# Rover_MDrv_V1_Sch.net
KiCad netlist of a schematic drawn in EAGLE
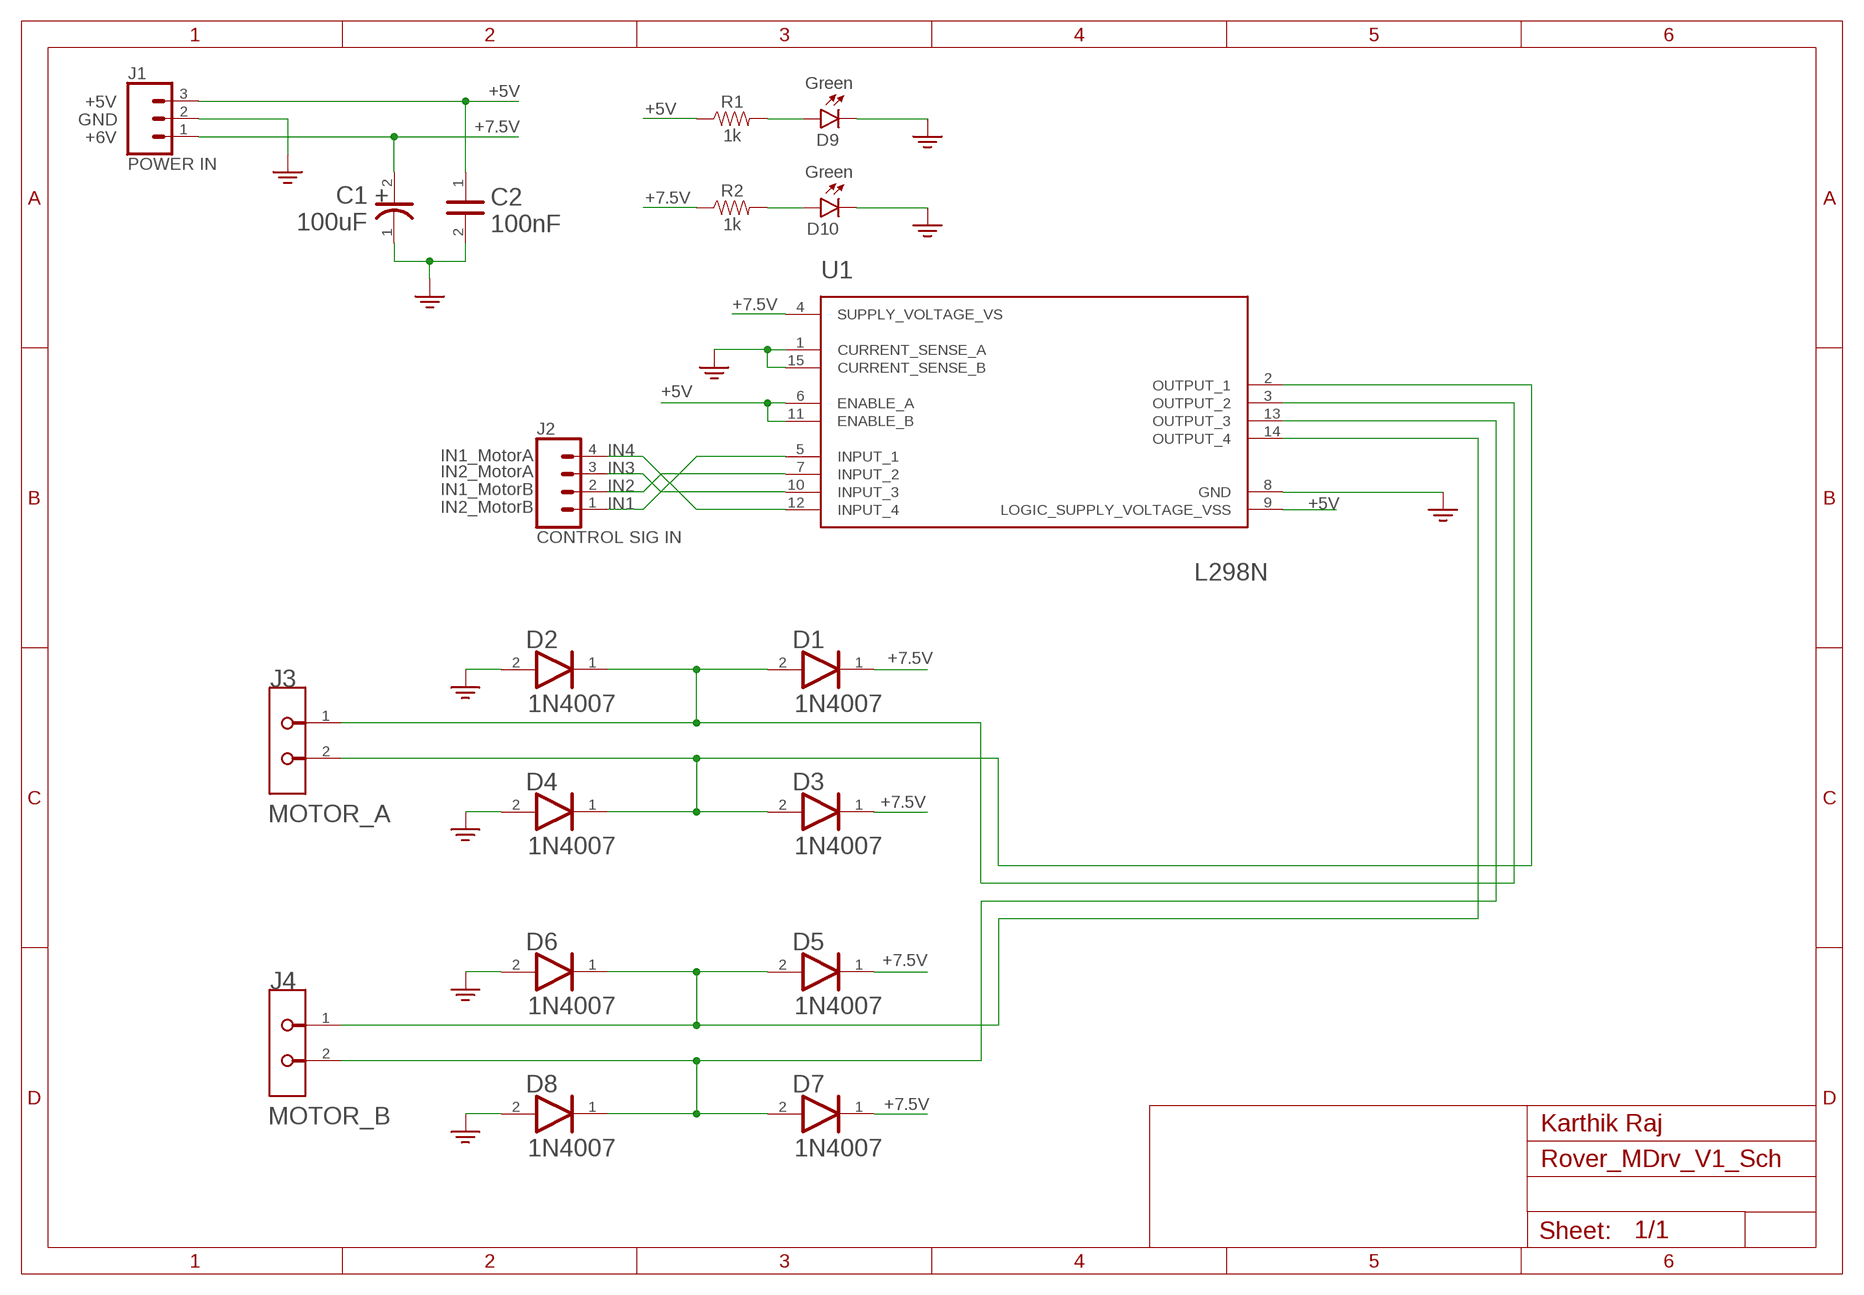
[diagram p0: schematic, sheet 1]

(export (version "E")
  (design (tool "Eeschema 10.0.6"))
  (components
    (comp (ref "C1")
      (value "100uF")
      (footprint "eagle-import:PANASONIC_EEU-FR1C101_0")
      (fields
        (field (name "DIGIKEY_PART_NUMBER") "P14391-ND")
        (field (name "MF") "Panasonic")
        (field (name "MOUSER_PART_NUMBER") "667-EEU-FR1C101")
      )
      (libsource (lib "eagle-import") (part "PANASONIC_EEU-FR1C101PANASONIC_EEU-FR1C101_0_0"))
    )
    (comp (ref "C2")
      (value "100nF")
      (footprint "eagle-import:AVX_CK05BX104K_0")
      (fields
        (field (name "DIGIKEY_PART_NUMBER") "1010-1198-ND")
        (field (name "MF") "AVX")
        (field (name "MOUSER_PART_NUMBER") "581-CK05BX104K")
      )
      (libsource (lib "eagle-import") (part "AVX_CK05BX104KAVX_CK05BX104K_0_0"))
    )
    (comp (ref "D1")
      (value "DIOTEC_1N4007DIOTEC_1N4007_0_0")
      (footprint "eagle-import:DIOTEC_1N4007_0")
      (fields (field (name "MF") "Diotec") (field (name "MPN") "1N4007"))
      (libsource (lib "eagle-import") (part "DIOTEC_1N4007DIOTEC_1N4007_0_0"))
    )
    (comp (ref "D2")
      (value "DIOTEC_1N4007DIOTEC_1N4007_0_0")
      (footprint "eagle-import:DIOTEC_1N4007_0")
      (fields (field (name "MF") "Diotec") (field (name "MPN") "1N4007"))
      (libsource (lib "eagle-import") (part "DIOTEC_1N4007DIOTEC_1N4007_0_0"))
    )
    (comp (ref "D3")
      (value "DIOTEC_1N4007DIOTEC_1N4007_0_0")
      (footprint "eagle-import:DIOTEC_1N4007_0")
      (fields (field (name "MF") "Diotec") (field (name "MPN") "1N4007"))
      (libsource (lib "eagle-import") (part "DIOTEC_1N4007DIOTEC_1N4007_0_0"))
    )
    (comp (ref "D4")
      (value "DIOTEC_1N4007DIOTEC_1N4007_0_0")
      (footprint "eagle-import:DIOTEC_1N4007_0")
      (fields (field (name "MF") "Diotec") (field (name "MPN") "1N4007"))
      (libsource (lib "eagle-import") (part "DIOTEC_1N4007DIOTEC_1N4007_0_0"))
    )
    (comp (ref "D5")
      (value "DIOTEC_1N4007DIOTEC_1N4007_0_0")
      (footprint "eagle-import:DIOTEC_1N4007_0")
      (fields (field (name "MF") "Diotec") (field (name "MPN") "1N4007"))
      (libsource (lib "eagle-import") (part "DIOTEC_1N4007DIOTEC_1N4007_0_0"))
    )
    (comp (ref "D6")
      (value "DIOTEC_1N4007DIOTEC_1N4007_0_0")
      (footprint "eagle-import:DIOTEC_1N4007_0")
      (fields (field (name "MF") "Diotec") (field (name "MPN") "1N4007"))
      (libsource (lib "eagle-import") (part "DIOTEC_1N4007DIOTEC_1N4007_0_0"))
    )
    (comp (ref "D7")
      (value "DIOTEC_1N4007DIOTEC_1N4007_0_0")
      (footprint "eagle-import:DIOTEC_1N4007_0")
      (fields (field (name "MF") "Diotec") (field (name "MPN") "1N4007"))
      (libsource (lib "eagle-import") (part "DIOTEC_1N4007DIOTEC_1N4007_0_0"))
    )
    (comp (ref "D8")
      (value "DIOTEC_1N4007DIOTEC_1N4007_0_0")
      (footprint "eagle-import:DIOTEC_1N4007_0")
      (fields (field (name "MF") "Diotec") (field (name "MPN") "1N4007"))
      (libsource (lib "eagle-import") (part "DIOTEC_1N4007DIOTEC_1N4007_0_0"))
    )
    (comp (ref "D9")
      (value "Green")
      (footprint "eagle-import:LED_3MM")
      (libsource (lib "eagle-import") (part "LED3MM"))
    )
    (comp (ref "D10")
      (value "Green")
      (footprint "eagle-import:LED_3MM")
      (libsource (lib "eagle-import") (part "LED3MM"))
    )
    (comp (ref "J1")
      (value "POWER IN")
      (footprint "eagle-import:1X03")
      (libsource (lib "eagle-import") (part "CONN_03"))
    )
    (comp (ref "J2")
      (value "CONTROL SIG IN")
      (footprint "eagle-import:1X04")
      (libsource (lib "eagle-import") (part "CONN_04PTH"))
    )
    (comp (ref "J3")
      (value "MOTOR_A")
      (footprint "eagle-import:TE_282837-2_0")
      (fields
        (field (name "DIGIKEY_PART_NUMBER") "A113320-ND")
        (field (name "MF") "TE")
        (field (name "MOUSER_PART_NUMBER") "571-2828372")
      )
      (libsource (lib "eagle-import") (part "TE_282837-2TE_282837-2_0_0"))
    )
    (comp (ref "J4")
      (value "MOTOR_B")
      (footprint "eagle-import:TE_282837-2_0")
      (fields
        (field (name "DIGIKEY_PART_NUMBER") "A113320-ND")
        (field (name "MF") "TE")
        (field (name "MOUSER_PART_NUMBER") "571-2828372")
      )
      (libsource (lib "eagle-import") (part "TE_282837-2TE_282837-2_0_0"))
    )
    (comp (ref "R1")
      (value "1k")
      (footprint "eagle-import:AXIAL-0.3")
      (libsource (lib "eagle-import") (part "RESISTORAXIAL-0.3"))
    )
    (comp (ref "R2")
      (value "1k")
      (footprint "eagle-import:AXIAL-0.3")
      (libsource (lib "eagle-import") (part "RESISTORAXIAL-0.3"))
    )
    (comp (ref "U1")
      (value "STMICROELECTRONICS_L298NSTMICROELECTRONICS_L298N_0_0")
      (footprint "eagle-import:STMICROELECTRONICS_L298N_0")
      (fields
        (field (name "DIGIKEY_PART_NUMBER") "497-1395-5-ND")
        (field (name "MF") "STMicroelectronics")
        (field (name "MOUSER_PART_NUMBER") "511-L298")
      )
      (libsource (lib "eagle-import") (part "STMICROELECTRONICS_L298NSTMICROELECTRONICS_L298N_0_0"))
    )
  )
  (nets
    (net (code "1") (name "/+5V") (class "Default")
      (node (ref "C2") (pin "1") (pinfunction "1_1") (pintype "bidirectional"))
      (node (ref "J1") (pin "3") (pinfunction "3_3") (pintype "passive"))
      (node (ref "R1") (pin "P$1") (pinfunction "1_P$1") (pintype "passive"))
      (node (ref "U1") (pin "11") (pinfunction "ENABLE_B_11") (pintype "bidirectional"))
      (node (ref "U1") (pin "6") (pinfunction "ENABLE_A_6") (pintype "bidirectional"))
      (node (ref "U1") (pin "9") (pinfunction "LOGIC_SUPPLY_VOLTAGE_VSS_9") (pintype "bidirectional"))
    )
    (net (code "2") (name "/+7.5V") (class "Default")
      (node (ref "C1") (pin "2") (pinfunction "ANODE_2") (pintype "bidirectional"))
      (node (ref "D1") (pin "1") (pinfunction "CATHODE_1") (pintype "passive"))
      (node (ref "D3") (pin "1") (pinfunction "CATHODE_1") (pintype "passive"))
      (node (ref "D5") (pin "1") (pinfunction "CATHODE_1") (pintype "passive"))
      (node (ref "D7") (pin "1") (pinfunction "CATHODE_1") (pintype "passive"))
      (node (ref "J1") (pin "1") (pinfunction "1_1") (pintype "passive"))
      (node (ref "R2") (pin "P$1") (pinfunction "1_P$1") (pintype "passive"))
      (node (ref "U1") (pin "4") (pinfunction "SUPPLY_VOLTAGE_VS_4") (pintype "bidirectional"))
    )
    (net (code "3") (name "/IN1") (class "Default")
      (node (ref "J2") (pin "1") (pinfunction "1_1") (pintype "passive"))
      (node (ref "U1") (pin "5") (pinfunction "INPUT_1_5") (pintype "bidirectional"))
    )
    (net (code "4") (name "/IN2") (class "Default")
      (node (ref "J2") (pin "2") (pinfunction "2_2") (pintype "passive"))
      (node (ref "U1") (pin "7") (pinfunction "INPUT_2_7") (pintype "bidirectional"))
    )
    (net (code "5") (name "/IN3") (class "Default")
      (node (ref "J2") (pin "3") (pinfunction "3_3") (pintype "passive"))
      (node (ref "U1") (pin "10") (pinfunction "INPUT_3_10") (pintype "bidirectional"))
    )
    (net (code "6") (name "/IN4") (class "Default")
      (node (ref "J2") (pin "4") (pinfunction "4_4") (pintype "passive"))
      (node (ref "U1") (pin "12") (pinfunction "INPUT_4_12") (pintype "bidirectional"))
    )
    (net (code "7") (name "GND2") (class "Default")
      (node (ref "C1") (pin "1") (pinfunction "CATHODE_1") (pintype "bidirectional"))
      (node (ref "C2") (pin "2") (pinfunction "2_2") (pintype "bidirectional"))
      (node (ref "D10") (pin "K") (pinfunction "C_K") (pintype "passive"))
      (node (ref "D2") (pin "2") (pinfunction "ANODE_2") (pintype "passive"))
      (node (ref "D4") (pin "2") (pinfunction "ANODE_2") (pintype "passive"))
      (node (ref "D6") (pin "2") (pinfunction "ANODE_2") (pintype "passive"))
      (node (ref "D8") (pin "2") (pinfunction "ANODE_2") (pintype "passive"))
      (node (ref "D9") (pin "K") (pinfunction "C_K") (pintype "passive"))
      (node (ref "J1") (pin "2") (pinfunction "2_2") (pintype "passive"))
      (node (ref "U1") (pin "1") (pinfunction "CURRENT_SENSE_A_1") (pintype "bidirectional"))
      (node (ref "U1") (pin "15") (pinfunction "CURRENT_SENSE_B_15") (pintype "bidirectional"))
      (node (ref "U1") (pin "8") (pinfunction "GND_8") (pintype "bidirectional"))
    )
    (net (code "8") (name "Net-(D1-ANODE)") (class "Default")
      (node (ref "D1") (pin "2") (pinfunction "ANODE_2") (pintype "passive"))
      (node (ref "D2") (pin "1") (pinfunction "CATHODE_1") (pintype "passive"))
      (node (ref "J3") (pin "1") (pinfunction "1_1") (pintype "passive"))
      (node (ref "U1") (pin "3") (pinfunction "OUTPUT_2_3") (pintype "bidirectional"))
    )
    (net (code "9") (name "Net-(D3-ANODE)") (class "Default")
      (node (ref "D3") (pin "2") (pinfunction "ANODE_2") (pintype "passive"))
      (node (ref "D4") (pin "1") (pinfunction "CATHODE_1") (pintype "passive"))
      (node (ref "J3") (pin "2") (pinfunction "2_2") (pintype "passive"))
      (node (ref "U1") (pin "2") (pinfunction "OUTPUT_1_2") (pintype "bidirectional"))
    )
    (net (code "10") (name "Net-(D5-ANODE)") (class "Default")
      (node (ref "D5") (pin "2") (pinfunction "ANODE_2") (pintype "passive"))
      (node (ref "D6") (pin "1") (pinfunction "CATHODE_1") (pintype "passive"))
      (node (ref "J4") (pin "1") (pinfunction "1_1") (pintype "passive"))
      (node (ref "U1") (pin "14") (pinfunction "OUTPUT_4_14") (pintype "bidirectional"))
    )
    (net (code "11") (name "Net-(D7-ANODE)") (class "Default")
      (node (ref "D7") (pin "2") (pinfunction "ANODE_2") (pintype "passive"))
      (node (ref "D8") (pin "1") (pinfunction "CATHODE_1") (pintype "passive"))
      (node (ref "J4") (pin "2") (pinfunction "2_2") (pintype "passive"))
      (node (ref "U1") (pin "13") (pinfunction "OUTPUT_3_13") (pintype "bidirectional"))
    )
    (net (code "12") (name "Net-(R1-2)") (class "Default")
      (node (ref "D9") (pin "A") (pinfunction "A_A") (pintype "passive"))
      (node (ref "R1") (pin "P$2") (pinfunction "2_P$2") (pintype "passive"))
    )
    (net (code "13") (name "Net-(R2-2)") (class "Default")
      (node (ref "D10") (pin "A") (pinfunction "A_A") (pintype "passive"))
      (node (ref "R2") (pin "P$2") (pinfunction "2_P$2") (pintype "passive"))
    )
  )
)
